# baseband_generator.net
KiCad netlist of a schematic drawn in EAGLE
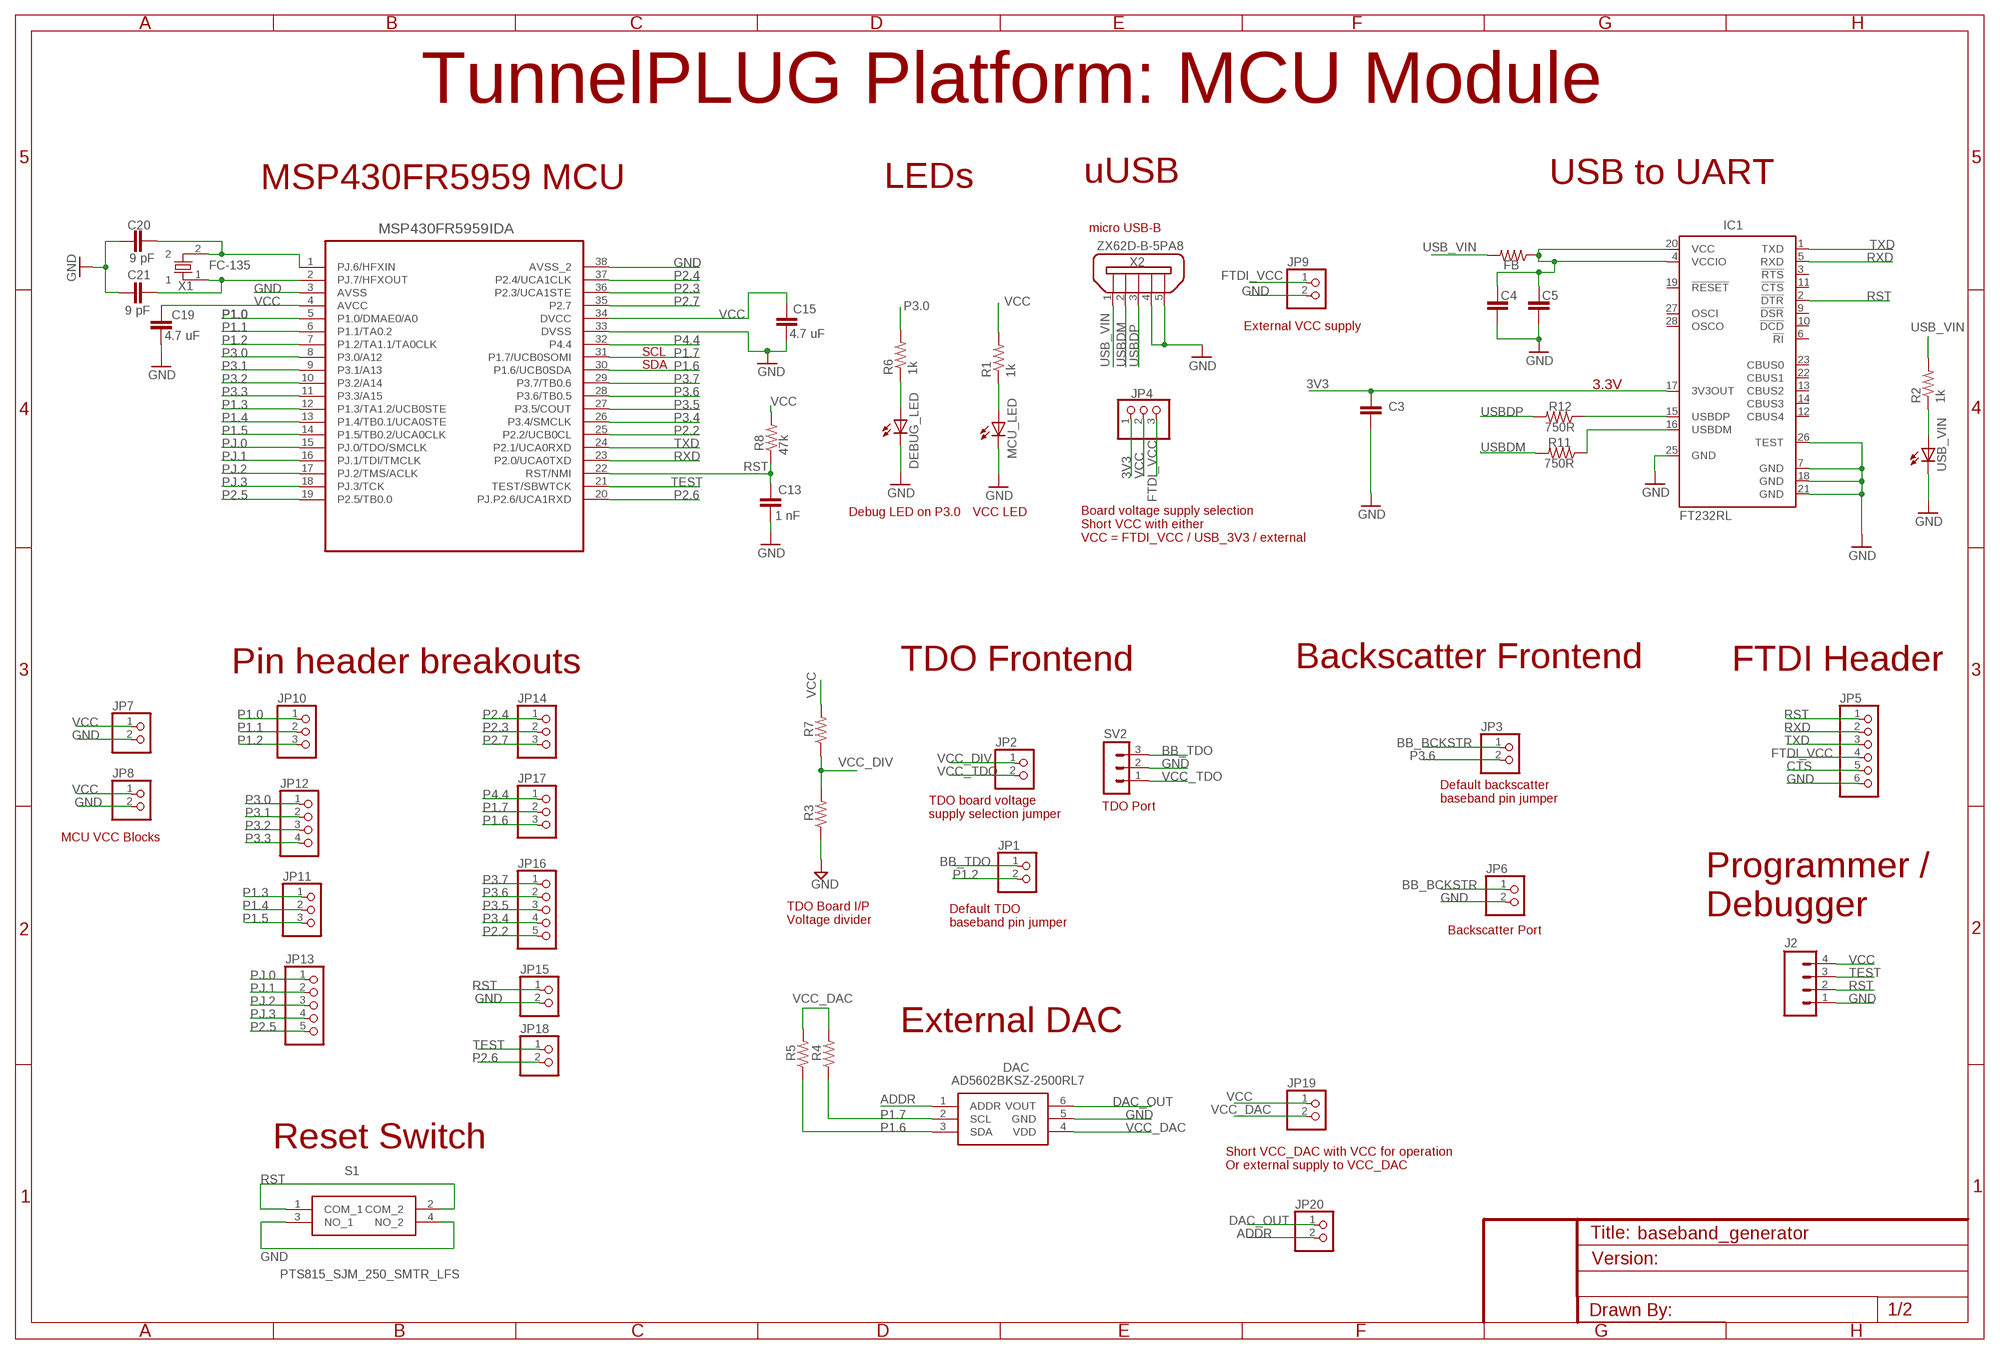
[diagram p0: schematic, sheet 1]

(export (version "E")
  (design (tool "Eeschema 10.0.6"))
  (components
    (comp (ref "C3")
      (value "0805_1")
      (footprint "eagle-import:0805_1PRIMARY")
      (libsource (lib "eagle-import") (part "0805_1"))
    )
    (comp (ref "C4")
      (value "0805_1")
      (footprint "eagle-import:0805_1PRIMARY")
      (libsource (lib "eagle-import") (part "0805_1"))
    )
    (comp (ref "C5")
      (value "0805_1")
      (footprint "eagle-import:0805_1PRIMARY")
      (libsource (lib "eagle-import") (part "0805_1"))
    )
    (comp (ref "C13")
      (value "1 nF")
      (footprint "eagle-import:C0603")
      (libsource (lib "eagle-import") (part "CAPACITOR"))
    )
    (comp (ref "C15")
      (value "4.7 uF")
      (footprint "eagle-import:C0603")
      (libsource (lib "eagle-import") (part "CAPACITOR"))
    )
    (comp (ref "C19")
      (value "4.7 uF")
      (footprint "eagle-import:C0603")
      (libsource (lib "eagle-import") (part "CAPACITOR"))
    )
    (comp (ref "C20")
      (value "9 pF")
      (footprint "eagle-import:C0603")
      (libsource (lib "eagle-import") (part "CAPACITOR"))
    )
    (comp (ref "C21")
      (value "9 pF")
      (footprint "eagle-import:C0603")
      (libsource (lib "eagle-import") (part "CAPACITOR"))
    )
    (comp (ref "DAC")
      (value "AD5602BKSZ-2500RL7")
      (footprint "eagle-import:SOT65P210X110-6N")
      (fields (field (name "MOUSER_PART_NUMBER") "584-AD5602BKSZ2500R7"))
      (libsource (lib "eagle-import") (part "AD5602BKSZ-2500RL7"))
    )
    (comp (ref "DEBUG_LED")
      (value "LED0603")
      (footprint "eagle-import:LED-0603")
      (libsource (lib "eagle-import") (part "LED0603"))
    )
    (comp (ref "FB")
      (value "RESISTOR0805-RES")
      (footprint "eagle-import:0805")
      (libsource (lib "eagle-import") (part "RESISTOR0805-RES"))
    )
    (comp (ref "IC1")
      (value "FT232RL")
      (footprint "eagle-import:SSOP28")
      (libsource (lib "eagle-import") (part "FT232RL"))
    )
    (comp (ref "J2")
      (value "MHDR1X4_1")
      (footprint "eagle-import:MHDR1X4_1PRIMARY")
      (libsource (lib "eagle-import") (part "MHDR1X4_1"))
    )
    (comp (ref "JP1")
      (value "PINHD-1X2/LOCK")
      (footprint "eagle-import:1X02_LOCK")
      (libsource (lib "eagle-import") (part "PINHD-1X2/LOCK"))
    )
    (comp (ref "JP2")
      (value "PINHD-1X2/LOCK")
      (footprint "eagle-import:1X02_LOCK")
      (libsource (lib "eagle-import") (part "PINHD-1X2/LOCK"))
    )
    (comp (ref "JP3")
      (value "PINHD-1X2/LOCK")
      (footprint "eagle-import:1X02_LOCK")
      (libsource (lib "eagle-import") (part "PINHD-1X2/LOCK"))
    )
    (comp (ref "JP4")
      (value "PINHD-1X3/LOCK")
      (footprint "eagle-import:1X03_LOCK")
      (libsource (lib "eagle-import") (part "PINHD-1X3/LOCK"))
    )
    (comp (ref "JP5")
      (value "PINHD-1X6/90")
      (footprint "eagle-import:1X06_90")
      (libsource (lib "eagle-import") (part "PINHD-1X6/90"))
    )
    (comp (ref "JP6")
      (value "PINHD-1X2")
      (footprint "eagle-import:1X02")
      (libsource (lib "eagle-import") (part "PINHD-1X2"))
    )
    (comp (ref "JP7")
      (value "PINHD-1X2")
      (footprint "eagle-import:1X02")
      (libsource (lib "eagle-import") (part "PINHD-1X2"))
    )
    (comp (ref "JP8")
      (value "PINHD-1X2")
      (footprint "eagle-import:1X02")
      (libsource (lib "eagle-import") (part "PINHD-1X2"))
    )
    (comp (ref "JP9")
      (value "PINHD-1X2")
      (footprint "eagle-import:1X02")
      (libsource (lib "eagle-import") (part "PINHD-1X2"))
    )
    (comp (ref "JP10")
      (value "PINHD-1X3")
      (footprint "eagle-import:1X03")
      (libsource (lib "eagle-import") (part "PINHD-1X3"))
    )
    (comp (ref "JP11")
      (value "PINHD-1X3")
      (footprint "eagle-import:1X03")
      (libsource (lib "eagle-import") (part "PINHD-1X3"))
    )
    (comp (ref "JP12")
      (value "PINHD-1X4")
      (footprint "eagle-import:1X04")
      (libsource (lib "eagle-import") (part "PINHD-1X4"))
    )
    (comp (ref "JP13")
      (value "PINHD-1X5")
      (footprint "eagle-import:1X05")
      (libsource (lib "eagle-import") (part "PINHD-1X5"))
    )
    (comp (ref "JP14")
      (value "PINHD-1X3")
      (footprint "eagle-import:1X03")
      (libsource (lib "eagle-import") (part "PINHD-1X3"))
    )
    (comp (ref "JP15")
      (value "PINHD-1X2")
      (footprint "eagle-import:1X02")
      (libsource (lib "eagle-import") (part "PINHD-1X2"))
    )
    (comp (ref "JP16")
      (value "PINHD-1X5")
      (footprint "eagle-import:1X05")
      (libsource (lib "eagle-import") (part "PINHD-1X5"))
    )
    (comp (ref "JP17")
      (value "PINHD-1X3")
      (footprint "eagle-import:1X03")
      (libsource (lib "eagle-import") (part "PINHD-1X3"))
    )
    (comp (ref "JP18")
      (value "PINHD-1X2")
      (footprint "eagle-import:1X02")
      (libsource (lib "eagle-import") (part "PINHD-1X2"))
    )
    (comp (ref "JP19")
      (value "PINHD-1X2")
      (footprint "eagle-import:1X02")
      (libsource (lib "eagle-import") (part "PINHD-1X2"))
    )
    (comp (ref "JP20")
      (value "PINHD-1X2")
      (footprint "eagle-import:1X02")
      (libsource (lib "eagle-import") (part "PINHD-1X2"))
    )
    (comp (ref "MCU_LED")
      (value "LED0603")
      (footprint "eagle-import:LED-0603")
      (libsource (lib "eagle-import") (part "LED0603"))
    )
    (comp (ref "R1")
      (value "1k")
      (footprint "eagle-import:0805")
      (libsource (lib "eagle-import") (part "RESISTOR0805-RES"))
    )
    (comp (ref "R2")
      (value "1k")
      (footprint "eagle-import:0805")
      (libsource (lib "eagle-import") (part "RESISTOR0805-RES"))
    )
    (comp (ref "R3")
      (value "R-US_R0603")
      (footprint "eagle-import:R0603")
      (libsource (lib "eagle-import") (part "R-US_R0603"))
    )
    (comp (ref "R4")
      (value "R-US_R0603")
      (footprint "eagle-import:R0603")
      (libsource (lib "eagle-import") (part "R-US_R0603"))
    )
    (comp (ref "R5")
      (value "R-US_R0603")
      (footprint "eagle-import:R0603")
      (libsource (lib "eagle-import") (part "R-US_R0603"))
    )
    (comp (ref "R6")
      (value "1k")
      (footprint "eagle-import:0805")
      (libsource (lib "eagle-import") (part "RESISTOR0805-RES"))
    )
    (comp (ref "R7")
      (value "R-US_R0603")
      (footprint "eagle-import:R0603")
      (libsource (lib "eagle-import") (part "R-US_R0603"))
    )
    (comp (ref "R8")
      (value "47k")
      (footprint "eagle-import:0805")
      (libsource (lib "eagle-import") (part "RESISTOR0805-RES"))
    )
    (comp (ref "R11")
      (value "750R")
      (footprint "eagle-import:0805")
      (libsource (lib "eagle-import") (part "RESISTOR0805-RES"))
    )
    (comp (ref "R12")
      (value "750R")
      (footprint "eagle-import:0805")
      (libsource (lib "eagle-import") (part "RESISTOR0805-RES"))
    )
    (comp (ref "S1")
      (value "PTS815_SJM_250_SMTR_LFS")
      (footprint "eagle-import:PTS815SJM250SMTRLFS")
      (fields
        (field (name "MANUFACTURER_PART_NUMBER") "PTS815 SJM 250 SMTR LFS")
        (field (name "MOUSER_PART_NUMBER") "611-PTS815SJM250SMTR")
      )
      (libsource (lib "eagle-import") (part "PTS815_SJM_250_SMTR_LFS"))
    )
    (comp (ref "SV2")
      (value "MA03-1")
      (footprint "eagle-import:MA03-1")
      (libsource (lib "eagle-import") (part "MA03-1"))
    )
    (comp (ref "U2")
      (value "MSP430FR5739IDAMSP430FR5959IDA")
      (footprint "eagle-import:SOP65P810X120-38N")
      (libsource (lib "eagle-import") (part "MSP430FR5739IDAMSP430FR5959IDA"))
    )
    (comp (ref "USB_VIN")
      (value "LED0603")
      (footprint "eagle-import:LED-0603")
      (libsource (lib "eagle-import") (part "LED0603"))
    )
    (comp (ref "X1")
      (value "FC-135")
      (footprint "eagle-import:FC-135_1PRIMARY")
      (libsource (lib "eagle-import") (part "FC-135"))
    )
    (comp (ref "X2")
      (value "ZX62D-B-5PA8")
      (footprint "eagle-import:ZX62D-B-5PA8")
      (fields (field (name "MF") "Hirose"))
      (libsource (lib "eagle-import") (part "ZX62D-B-5PA8"))
    )
  )
  (nets
    (net (code "1") (name "3V3") (class "Default")
      (node (ref "C3") (pin "1") (pinfunction "1_1") (pintype "passive"))
      (node (ref "IC1") (pin "17") (pinfunction "3V3OUT_17") (pintype "output"))
      (node (ref "JP4") (pin "1") (pinfunction "1_1") (pintype "passive"))
    )
    (net (code "2") (name "ADDR") (class "Default")
      (node (ref "DAC") (pin "1") (pinfunction "ADDR_1") (pintype "bidirectional"))
      (node (ref "JP20") (pin "2") (pinfunction "2_2") (pintype "passive"))
    )
    (net (code "3") (name "BB_BCKSTR") (class "Default")
      (node (ref "JP3") (pin "1") (pinfunction "1_1") (pintype "passive"))
      (node (ref "JP6") (pin "1") (pinfunction "1_1") (pintype "passive"))
    )
    (net (code "4") (name "BB_TDO") (class "Default")
      (node (ref "JP1") (pin "1") (pinfunction "1_1") (pintype "passive"))
      (node (ref "SV2") (pin "3") (pinfunction "3_3") (pintype "passive"))
    )
    (net (code "5") (name "CTS") (class "Default")
      (node (ref "JP5") (pin "5") (pinfunction "5_5") (pintype "passive"))
    )
    (net (code "6") (name "DAC_OUT") (class "Default")
      (node (ref "DAC") (pin "6") (pinfunction "VOUT_6") (pintype "bidirectional"))
      (node (ref "JP20") (pin "1") (pinfunction "1_1") (pintype "passive"))
    )
    (net (code "7") (name "FTDI_VCC") (class "Default")
      (node (ref "JP4") (pin "3") (pinfunction "3_3") (pintype "passive"))
      (node (ref "JP5") (pin "4") (pinfunction "4_4") (pintype "passive"))
      (node (ref "JP9") (pin "1") (pinfunction "1_1") (pintype "passive"))
    )
    (net (code "8") (name "GND") (class "Default")
      (node (ref "C13") (pin "2") (pinfunction "2_2") (pintype "passive"))
      (node (ref "C15") (pin "1") (pinfunction "1_1") (pintype "passive"))
      (node (ref "C19") (pin "2") (pinfunction "2_2") (pintype "passive"))
      (node (ref "C20") (pin "2") (pinfunction "2_2") (pintype "passive"))
      (node (ref "C21") (pin "2") (pinfunction "2_2") (pintype "passive"))
      (node (ref "C3") (pin "2") (pinfunction "2_2") (pintype "passive"))
      (node (ref "C4") (pin "2") (pinfunction "2_2") (pintype "passive"))
      (node (ref "C5") (pin "2") (pinfunction "2_2") (pintype "passive"))
      (node (ref "DAC") (pin "5") (pinfunction "GND_5") (pintype "bidirectional"))
      (node (ref "DEBUG_LED") (pin "C") (pinfunction "C_C") (pintype "passive"))
      (node (ref "IC1") (pin "18") (pinfunction "GND_18") (pintype "power_in"))
      (node (ref "IC1") (pin "21") (pinfunction "GND_21") (pintype "power_in"))
      (node (ref "IC1") (pin "25") (pinfunction "GND_25") (pintype "power_in"))
      (node (ref "IC1") (pin "26") (pinfunction "TEST_26") (pintype "input"))
      (node (ref "IC1") (pin "7") (pinfunction "GND_7") (pintype "power_in"))
      (node (ref "J2") (pin "1") (pinfunction "1_1") (pintype "passive"))
      (node (ref "JP15") (pin "2") (pinfunction "2_2") (pintype "passive"))
      (node (ref "JP5") (pin "6") (pinfunction "6_6") (pintype "passive"))
      (node (ref "JP6") (pin "2") (pinfunction "2_2") (pintype "passive"))
      (node (ref "JP7") (pin "2") (pinfunction "2_2") (pintype "passive"))
      (node (ref "JP8") (pin "2") (pinfunction "2_2") (pintype "passive"))
      (node (ref "JP9") (pin "2") (pinfunction "2_2") (pintype "passive"))
      (node (ref "MCU_LED") (pin "C") (pinfunction "C_C") (pintype "passive"))
      (node (ref "R3") (pin "1") (pinfunction "1_1") (pintype "passive"))
      (node (ref "S1") (pin "3") (pinfunction "NO_1_3") (pintype "bidirectional"))
      (node (ref "S1") (pin "4") (pinfunction "NO_2_4") (pintype "bidirectional"))
      (node (ref "SV2") (pin "2") (pinfunction "2_2") (pintype "passive"))
      (node (ref "U2") (pin "3") (pinfunction "AVSS_3") (pintype "passive"))
      (node (ref "U2") (pin "33") (pinfunction "DVSS_33") (pintype "bidirectional"))
      (node (ref "U2") (pin "38") (pinfunction "AVSS_2_38") (pintype "bidirectional"))
      (node (ref "USB_VIN") (pin "C") (pinfunction "C_C") (pintype "passive"))
      (node (ref "X2") (pin "4") (pinfunction "4_4") (pintype "passive"))
      (node (ref "X2") (pin "5") (pinfunction "5_5") (pintype "passive"))
    )
    (net (code "9") (name "Net-(DEBUG_LED-PadA)") (class "Default")
      (node (ref "DEBUG_LED") (pin "A") (pinfunction "A_A") (pintype "passive"))
      (node (ref "R6") (pin "1") (pinfunction "1_1") (pintype "passive"))
    )
    (net (code "10") (name "Net-(IC1-USBDM)") (class "Default")
      (node (ref "IC1") (pin "16") (pinfunction "USBDM_16") (pintype "bidirectional"))
      (node (ref "R11") (pin "1") (pinfunction "1_1") (pintype "passive"))
    )
    (net (code "11") (name "Net-(IC1-USBDP)") (class "Default")
      (node (ref "IC1") (pin "15") (pinfunction "USBDP_15") (pintype "bidirectional"))
      (node (ref "R12") (pin "1") (pinfunction "1_1") (pintype "passive"))
    )
    (net (code "12") (name "Net-(IC1-VCC)") (class "Default")
      (node (ref "C4") (pin "1") (pinfunction "1_1") (pintype "passive"))
      (node (ref "C5") (pin "1") (pinfunction "1_1") (pintype "passive"))
      (node (ref "FB") (pin "1") (pinfunction "1_1") (pintype "passive"))
      (node (ref "IC1") (pin "20") (pinfunction "VCC_20") (pintype "power_in"))
      (node (ref "IC1") (pin "4") (pinfunction "VCCIO_4") (pintype "power_in"))
    )
    (net (code "13") (name "Net-(MCU_LED-PadA)") (class "Default")
      (node (ref "MCU_LED") (pin "A") (pinfunction "A_A") (pintype "passive"))
      (node (ref "R1") (pin "1") (pinfunction "1_1") (pintype "passive"))
    )
    (net (code "14") (name "Net-(R2-Pad1)") (class "Default")
      (node (ref "R2") (pin "1") (pinfunction "1_1") (pintype "passive"))
      (node (ref "USB_VIN") (pin "A") (pinfunction "A_A") (pintype "passive"))
    )
    (net (code "15") (name "Net-(U2-PJ.6{slash}HFXIN)") (class "Default")
      (node (ref "C20") (pin "1") (pinfunction "1_1") (pintype "passive"))
      (node (ref "U2") (pin "1") (pinfunction "PJ.6/HFXIN_1") (pintype "power_in"))
      (node (ref "X1") (pin "2") (pinfunction "2_2") (pintype "bidirectional"))
    )
    (net (code "16") (name "Net-(U2-PJ.7{slash}HFXOUT)") (class "Default")
      (node (ref "C21") (pin "1") (pinfunction "1_1") (pintype "passive"))
      (node (ref "U2") (pin "2") (pinfunction "PJ.7/HFXOUT_2") (pintype "power_in"))
      (node (ref "X1") (pin "1") (pinfunction "1_1") (pintype "bidirectional"))
    )
    (net (code "17") (name "P1.0") (class "Default")
      (node (ref "JP10") (pin "1") (pinfunction "1_1") (pintype "passive"))
      (node (ref "U2") (pin "5") (pinfunction "P1.0/DMAE0/A0_5") (pintype "input"))
    )
    (net (code "18") (name "P1.1") (class "Default")
      (node (ref "JP10") (pin "2") (pinfunction "2_2") (pintype "passive"))
      (node (ref "U2") (pin "6") (pinfunction "P1.1/TA0.2_6") (pintype "input"))
    )
    (net (code "19") (name "P1.2") (class "Default")
      (node (ref "JP1") (pin "2") (pinfunction "2_2") (pintype "passive"))
      (node (ref "JP10") (pin "3") (pinfunction "3_3") (pintype "passive"))
      (node (ref "U2") (pin "7") (pinfunction "P1.2/TA1.1/TA0CLK_7") (pintype "bidirectional"))
    )
    (net (code "20") (name "P1.3") (class "Default")
      (node (ref "JP11") (pin "1") (pinfunction "1_1") (pintype "passive"))
      (node (ref "U2") (pin "12") (pinfunction "P1.3/TA1.2/UCB0STE_12") (pintype "bidirectional"))
    )
    (net (code "21") (name "P1.4") (class "Default")
      (node (ref "JP11") (pin "2") (pinfunction "2_2") (pintype "passive"))
      (node (ref "U2") (pin "13") (pinfunction "P1.4/TB0.1/UCA0STE_13") (pintype "bidirectional"))
    )
    (net (code "22") (name "P1.5") (class "Default")
      (node (ref "JP11") (pin "3") (pinfunction "3_3") (pintype "passive"))
      (node (ref "U2") (pin "14") (pinfunction "P1.5/TB0.2/UCA0CLK_14") (pintype "bidirectional"))
    )
    (net (code "23") (name "P1.6") (class "Default")
      (node (ref "DAC") (pin "3") (pinfunction "SDA_3") (pintype "bidirectional"))
      (node (ref "JP17") (pin "3") (pinfunction "3_3") (pintype "passive"))
      (node (ref "R5") (pin "1") (pinfunction "1_1") (pintype "passive"))
      (node (ref "U2") (pin "30") (pinfunction "P1.6/UCB0SDA_30") (pintype "bidirectional"))
    )
    (net (code "24") (name "P1.7") (class "Default")
      (node (ref "DAC") (pin "2") (pinfunction "SCL_2") (pintype "bidirectional"))
      (node (ref "JP17") (pin "2") (pinfunction "2_2") (pintype "passive"))
      (node (ref "R4") (pin "1") (pinfunction "1_1") (pintype "passive"))
      (node (ref "U2") (pin "31") (pinfunction "P1.7/UCB0SOMI_31") (pintype "bidirectional"))
    )
    (net (code "25") (name "P2.2") (class "Default")
      (node (ref "JP16") (pin "5") (pinfunction "5_5") (pintype "passive"))
      (node (ref "U2") (pin "25") (pinfunction "P2.2/UCB0CL_25") (pintype "bidirectional"))
    )
    (net (code "26") (name "P2.3") (class "Default")
      (node (ref "JP14") (pin "2") (pinfunction "2_2") (pintype "passive"))
      (node (ref "U2") (pin "36") (pinfunction "P2.3/UCA1STE_36") (pintype "bidirectional"))
    )
    (net (code "27") (name "P2.4") (class "Default")
      (node (ref "JP14") (pin "1") (pinfunction "1_1") (pintype "passive"))
      (node (ref "U2") (pin "37") (pinfunction "P2.4/UCA1CLK_37") (pintype "bidirectional"))
    )
    (net (code "28") (name "P2.5") (class "Default")
      (node (ref "JP13") (pin "5") (pinfunction "5_5") (pintype "passive"))
      (node (ref "U2") (pin "19") (pinfunction "P2.5/TB0.0_19") (pintype "bidirectional"))
    )
    (net (code "29") (name "P2.6") (class "Default")
      (node (ref "JP18") (pin "2") (pinfunction "2_2") (pintype "passive"))
      (node (ref "U2") (pin "20") (pinfunction "PJ.P2.6/UCA1RXD_20") (pintype "bidirectional"))
    )
    (net (code "30") (name "P2.7") (class "Default")
      (node (ref "JP14") (pin "3") (pinfunction "3_3") (pintype "passive"))
      (node (ref "U2") (pin "35") (pinfunction "P2.7_35") (pintype "bidirectional"))
    )
    (net (code "31") (name "P3.0") (class "Default")
      (node (ref "JP12") (pin "1") (pinfunction "1_1") (pintype "passive"))
      (node (ref "R6") (pin "2") (pinfunction "2_2") (pintype "passive"))
      (node (ref "U2") (pin "8") (pinfunction "P3.0/A12_8") (pintype "bidirectional"))
    )
    (net (code "32") (name "P3.1") (class "Default")
      (node (ref "JP12") (pin "2") (pinfunction "2_2") (pintype "passive"))
      (node (ref "U2") (pin "9") (pinfunction "P3.1/A13_9") (pintype "bidirectional"))
    )
    (net (code "33") (name "P3.2") (class "Default")
      (node (ref "JP12") (pin "3") (pinfunction "3_3") (pintype "passive"))
      (node (ref "U2") (pin "10") (pinfunction "P3.2/A14_10") (pintype "bidirectional"))
    )
    (net (code "34") (name "P3.3") (class "Default")
      (node (ref "JP12") (pin "4") (pinfunction "4_4") (pintype "passive"))
      (node (ref "U2") (pin "11") (pinfunction "P3.3/A15_11") (pintype "bidirectional"))
    )
    (net (code "35") (name "P3.4") (class "Default")
      (node (ref "JP16") (pin "4") (pinfunction "4_4") (pintype "passive"))
      (node (ref "U2") (pin "26") (pinfunction "P3.4/SMCLK_26") (pintype "bidirectional"))
    )
    (net (code "36") (name "P3.5") (class "Default")
      (node (ref "JP16") (pin "3") (pinfunction "3_3") (pintype "passive"))
      (node (ref "U2") (pin "27") (pinfunction "P3.5/COUT_27") (pintype "bidirectional"))
    )
    (net (code "37") (name "P3.6") (class "Default")
      (node (ref "JP16") (pin "2") (pinfunction "2_2") (pintype "passive"))
      (node (ref "JP3") (pin "2") (pinfunction "2_2") (pintype "passive"))
      (node (ref "U2") (pin "28") (pinfunction "P3.6/TB0.5_28") (pintype "bidirectional"))
    )
    (net (code "38") (name "P3.7") (class "Default")
      (node (ref "JP16") (pin "1") (pinfunction "1_1") (pintype "passive"))
      (node (ref "U2") (pin "29") (pinfunction "P3.7/TB0.6_29") (pintype "bidirectional"))
    )
    (net (code "39") (name "P4.4") (class "Default")
      (node (ref "JP17") (pin "1") (pinfunction "1_1") (pintype "passive"))
      (node (ref "U2") (pin "32") (pinfunction "P4.4_32") (pintype "bidirectional"))
    )
    (net (code "40") (name "PJ.0") (class "Default")
      (node (ref "JP13") (pin "1") (pinfunction "1_1") (pintype "passive"))
      (node (ref "U2") (pin "15") (pinfunction "PJ.0/TDO/SMCLK_15") (pintype "bidirectional"))
    )
    (net (code "41") (name "PJ.1") (class "Default")
      (node (ref "JP13") (pin "2") (pinfunction "2_2") (pintype "passive"))
      (node (ref "U2") (pin "16") (pinfunction "PJ.1/TDI/TMCLK_16") (pintype "passive"))
    )
    (net (code "42") (name "PJ.2") (class "Default")
      (node (ref "JP13") (pin "3") (pinfunction "3_3") (pintype "passive"))
      (node (ref "U2") (pin "17") (pinfunction "PJ.2/TMS/ACLK_17") (pintype "passive"))
    )
    (net (code "43") (name "PJ.3") (class "Default")
      (node (ref "JP13") (pin "4") (pinfunction "4_4") (pintype "passive"))
      (node (ref "U2") (pin "18") (pinfunction "PJ.3/TCK_18") (pintype "bidirectional"))
    )
    (net (code "44") (name "RST") (class "Default")
      (node (ref "C13") (pin "1") (pinfunction "1_1") (pintype "passive"))
      (node (ref "IC1") (pin "2") (pinfunction "~{DTR}_2") (pintype "output"))
      (node (ref "J2") (pin "2") (pinfunction "2_2") (pintype "passive"))
      (node (ref "JP15") (pin "1") (pinfunction "1_1") (pintype "passive"))
      (node (ref "JP5") (pin "1") (pinfunction "1_1") (pintype "passive"))
      (node (ref "R8") (pin "1") (pinfunction "1_1") (pintype "passive"))
      (node (ref "S1") (pin "1") (pinfunction "COM_1_1") (pintype "bidirectional"))
      (node (ref "S1") (pin "2") (pinfunction "COM_2_2") (pintype "bidirectional"))
      (node (ref "U2") (pin "22") (pinfunction "RST/NMI_22") (pintype "bidirectional"))
    )
    (net (code "45") (name "RXD") (class "Default")
      (node (ref "IC1") (pin "5") (pinfunction "RXD_5") (pintype "input"))
      (node (ref "JP5") (pin "2") (pinfunction "2_2") (pintype "passive"))
      (node (ref "U2") (pin "23") (pinfunction "P2.0/UCA0TXD_23") (pintype "bidirectional"))
    )
    (net (code "46") (name "TEST") (class "Default")
      (node (ref "J2") (pin "3") (pinfunction "3_3") (pintype "passive"))
      (node (ref "JP18") (pin "1") (pinfunction "1_1") (pintype "passive"))
      (node (ref "U2") (pin "21") (pinfunction "TEST/SBWTCK_21") (pintype "bidirectional"))
    )
    (net (code "47") (name "TXD") (class "Default")
      (node (ref "IC1") (pin "1") (pinfunction "TXD_1") (pintype "output"))
      (node (ref "JP5") (pin "3") (pinfunction "3_3") (pintype "passive"))
      (node (ref "U2") (pin "24") (pinfunction "P2.1/UCA0RXD_24") (pintype "bidirectional"))
    )
    (net (code "48") (name "USBDM") (class "Default")
      (node (ref "R11") (pin "2") (pinfunction "2_2") (pintype "passive"))
      (node (ref "X2") (pin "2") (pinfunction "2_2") (pintype "passive"))
    )
    (net (code "49") (name "USBDP") (class "Default")
      (node (ref "R12") (pin "2") (pinfunction "2_2") (pintype "passive"))
      (node (ref "X2") (pin "3") (pinfunction "3_3") (pintype "passive"))
    )
    (net (code "50") (name "USB_VIN") (class "Default")
      (node (ref "FB") (pin "2") (pinfunction "2_2") (pintype "passive"))
      (node (ref "R2") (pin "2") (pinfunction "2_2") (pintype "passive"))
      (node (ref "X2") (pin "1") (pinfunction "1_1") (pintype "passive"))
    )
    (net (code "51") (name "VCC") (class "Default")
      (node (ref "C15") (pin "2") (pinfunction "2_2") (pintype "passive"))
      (node (ref "C19") (pin "1") (pinfunction "1_1") (pintype "passive"))
      (node (ref "J2") (pin "4") (pinfunction "4_4") (pintype "passive"))
      (node (ref "JP19") (pin "1") (pinfunction "1_1") (pintype "passive"))
      (node (ref "JP4") (pin "2") (pinfunction "2_2") (pintype "passive"))
      (node (ref "JP7") (pin "1") (pinfunction "1_1") (pintype "passive"))
      (node (ref "JP8") (pin "1") (pinfunction "1_1") (pintype "passive"))
      (node (ref "R1") (pin "2") (pinfunction "2_2") (pintype "passive"))
      (node (ref "R7") (pin "2") (pinfunction "2_2") (pintype "passive"))
      (node (ref "R8") (pin "2") (pinfunction "2_2") (pintype "passive"))
      (node (ref "U2") (pin "34") (pinfunction "DVCC_34") (pintype "bidirectional"))
      (node (ref "U2") (pin "4") (pinfunction "AVCC_4") (pintype "power_in"))
    )
    (net (code "52") (name "VCC_DAC") (class "Default")
      (node (ref "DAC") (pin "4") (pinfunction "VDD_4") (pintype "bidirectional"))
      (node (ref "JP19") (pin "2") (pinfunction "2_2") (pintype "passive"))
      (node (ref "R4") (pin "2") (pinfunction "2_2") (pintype "passive"))
      (node (ref "R5") (pin "2") (pinfunction "2_2") (pintype "passive"))
    )
    (net (code "53") (name "VCC_DIV") (class "Default")
      (node (ref "JP2") (pin "1") (pinfunction "1_1") (pintype "passive"))
      (node (ref "R3") (pin "2") (pinfunction "2_2") (pintype "passive"))
      (node (ref "R7") (pin "1") (pinfunction "1_1") (pintype "passive"))
    )
    (net (code "54") (name "VCC_TDO") (class "Default")
      (node (ref "JP2") (pin "2") (pinfunction "2_2") (pintype "passive"))
      (node (ref "SV2") (pin "1") (pinfunction "1_1") (pintype "passive"))
    )
    (net (code "55") (name "unconnected-(IC1-CBUS0-Pad23)") (class "Default")
      (node (ref "IC1") (pin "23") (pinfunction "CBUS0_23") (pintype "bidirectional"))
    )
    (net (code "56") (name "unconnected-(IC1-CBUS1-Pad22)") (class "Default")
      (node (ref "IC1") (pin "22") (pinfunction "CBUS1_22") (pintype "bidirectional"))
    )
    (net (code "57") (name "unconnected-(IC1-CBUS2-Pad13)") (class "Default")
      (node (ref "IC1") (pin "13") (pinfunction "CBUS2_13") (pintype "bidirectional"))
    )
    (net (code "58") (name "unconnected-(IC1-CBUS3-Pad14)") (class "Default")
      (node (ref "IC1") (pin "14") (pinfunction "CBUS3_14") (pintype "bidirectional"))
    )
    (net (code "59") (name "unconnected-(IC1-CBUS4-Pad12)") (class "Default")
      (node (ref "IC1") (pin "12") (pinfunction "CBUS4_12") (pintype "bidirectional"))
    )
    (net (code "60") (name "unconnected-(IC1-OSCI-Pad27)") (class "Default")
      (node (ref "IC1") (pin "27") (pinfunction "OSCI_27") (pintype "input"))
    )
    (net (code "61") (name "unconnected-(IC1-OSCO-Pad28)") (class "Default")
      (node (ref "IC1") (pin "28") (pinfunction "OSCO_28") (pintype "output"))
    )
    (net (code "62") (name "unconnected-(IC1-~{CTS}-Pad11)") (class "Default")
      (node (ref "IC1") (pin "11") (pinfunction "~{CTS}_11") (pintype "input"))
    )
    (net (code "63") (name "unconnected-(IC1-~{DCD}-Pad10)") (class "Default")
      (node (ref "IC1") (pin "10") (pinfunction "~{DCD}_10") (pintype "input"))
    )
    (net (code "64") (name "unconnected-(IC1-~{DSR}-Pad9)") (class "Default")
      (node (ref "IC1") (pin "9") (pinfunction "~{DSR}_9") (pintype "input"))
    )
    (net (code "65") (name "unconnected-(IC1-~{RESET}-Pad19)") (class "Default")
      (node (ref "IC1") (pin "19") (pinfunction "~{RESET}_19") (pintype "input"))
    )
    (net (code "66") (name "unconnected-(IC1-~{RI}-Pad6)") (class "Default")
      (node (ref "IC1") (pin "6") (pinfunction "~{RI}_6") (pintype "input"))
    )
    (net (code "67") (name "unconnected-(IC1-~{RTS}-Pad3)") (class "Default")
      (node (ref "IC1") (pin "3") (pinfunction "~{RTS}_3") (pintype "output"))
    )
  )
)
